# Arduino_StepperPrototype.net
KiCad netlist of a schematic drawn in Altium Designer
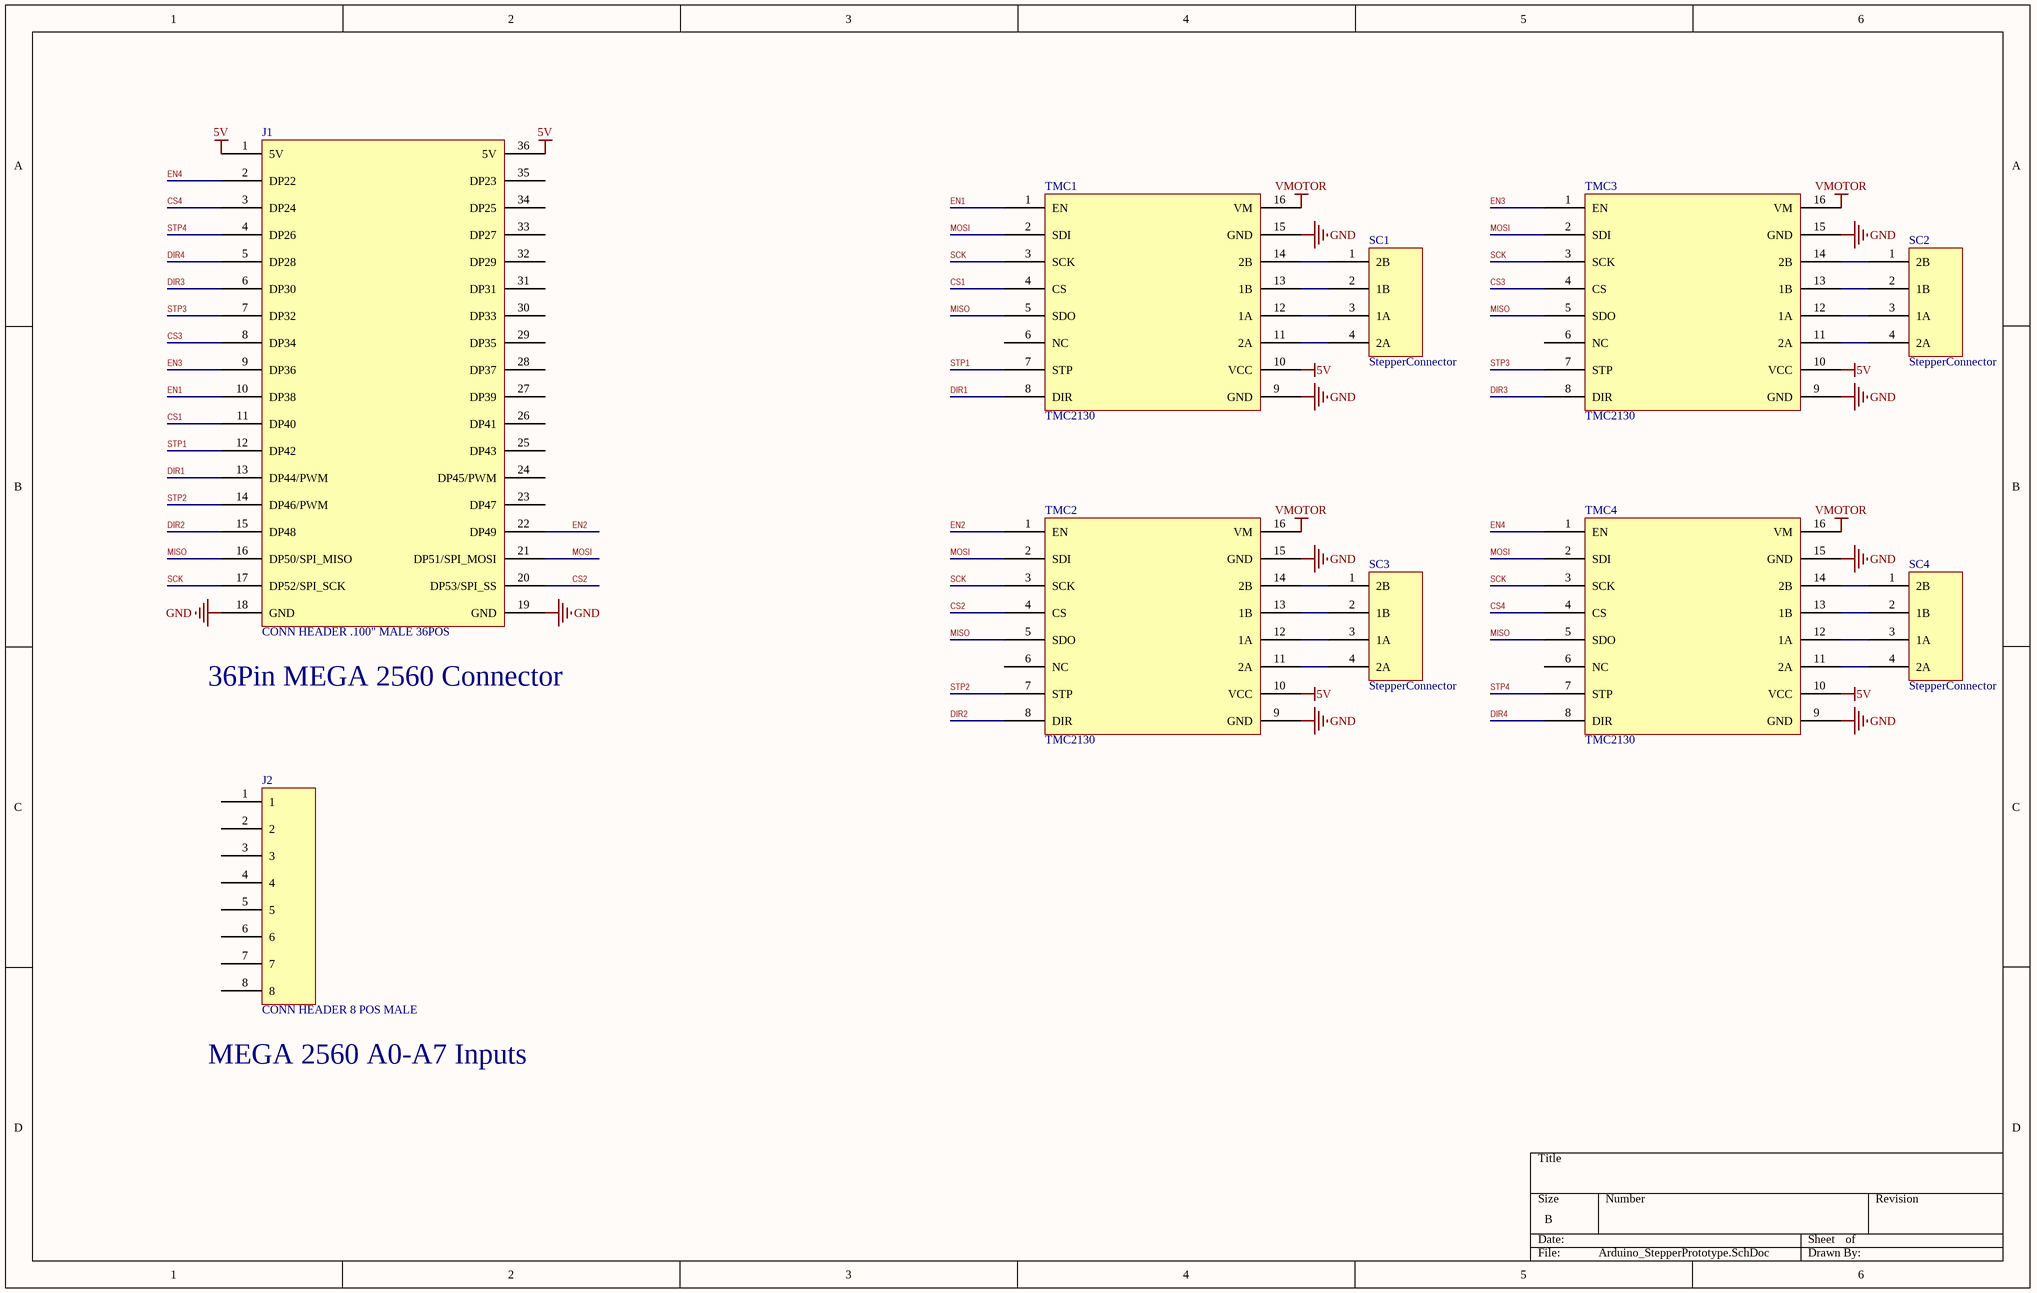
[diagram p0: Arduino_StepperPrototype.SchDoc]

(export (version "E")
  (design (tool "Eeschema 10.0.6"))
  (components
    (comp (ref "J1")
      (value "CONN HEADER .100\" MALE 36POS")
      (footprint "DIP36_MALE")
      (description "CONN HEADER .100\" DUAL STR 36POS")
      (fields
        (field (name "MANUFACTURER") "Sullins")
        (field (name "MANUFACTURER PART NUMBER") "PREC018DAAN-RC")
      )
      (libsource (lib "Arduino_StepperPrototype") (part "PREC018DAAN-RC"))
    )
    (comp (ref "J2")
      (value "CONN HEADER 8 POS MALE")
      (footprint "DIP8_MALE")
      (fields
        (field (name "MANUFACTURER") "Sullins")
        (field (name "MANUFACTURER PART NUMBER") "PREC008SAAN-RC")
      )
      (libsource (lib "Arduino_StepperPrototype") (part "PREC008SAAN-RC"))
    )
    (comp (ref "SC1")
      (value "StepperConnector")
      (footprint "DIP4")
      (libsource (lib "Arduino_StepperPrototype") (part "StepperConn"))
    )
    (comp (ref "SC2")
      (value "StepperConnector")
      (footprint "DIP4")
      (libsource (lib "Arduino_StepperPrototype") (part "StepperConn"))
    )
    (comp (ref "SC3")
      (value "StepperConnector")
      (footprint "DIP4")
      (libsource (lib "Arduino_StepperPrototype") (part "StepperConn"))
    )
    (comp (ref "SC4")
      (value "StepperConnector")
      (footprint "DIP4")
      (libsource (lib "Arduino_StepperPrototype") (part "StepperConn"))
    )
    (comp (ref "TMC1")
      (value "TMC2130")
      (footprint "DIP16_Stepper")
      (description "Knockoff SilentStepStick")
      (libsource (lib "Arduino_StepperPrototype") (part "SilentStepStick_BigTreeTech_TMC2130V1.1"))
    )
    (comp (ref "TMC2")
      (value "TMC2130")
      (footprint "DIP16_Stepper")
      (description "Knockoff SilentStepStick")
      (libsource (lib "Arduino_StepperPrototype") (part "SilentStepStick_BigTreeTech_TMC2130V1.1"))
    )
    (comp (ref "TMC3")
      (value "TMC2130")
      (footprint "DIP16_Stepper")
      (description "Knockoff SilentStepStick")
      (libsource (lib "Arduino_StepperPrototype") (part "SilentStepStick_BigTreeTech_TMC2130V1.1"))
    )
    (comp (ref "TMC4")
      (value "TMC2130")
      (footprint "DIP16_Stepper")
      (description "Knockoff SilentStepStick")
      (libsource (lib "Arduino_StepperPrototype") (part "SilentStepStick_BigTreeTech_TMC2130V1.1"))
    )
  )
  (nets
    (net (code "1") (name "/CS1") (class "Default")
      (node (ref "J1") (pin "11") (pinfunction "DP40_11") (pintype "passive"))
      (node (ref "TMC1") (pin "4") (pinfunction "CS_4") (pintype "passive"))
    )
    (net (code "2") (name "/CS2") (class "Default")
      (node (ref "J1") (pin "20") (pinfunction "DP53/SPI_SS_20") (pintype "passive"))
      (node (ref "TMC2") (pin "4") (pinfunction "CS_4") (pintype "passive"))
    )
    (net (code "3") (name "/CS3") (class "Default")
      (node (ref "J1") (pin "8") (pinfunction "DP34_8") (pintype "passive"))
      (node (ref "TMC3") (pin "4") (pinfunction "CS_4") (pintype "passive"))
    )
    (net (code "4") (name "/CS4") (class "Default")
      (node (ref "J1") (pin "3") (pinfunction "DP24_3") (pintype "passive"))
      (node (ref "TMC4") (pin "4") (pinfunction "CS_4") (pintype "passive"))
    )
    (net (code "5") (name "/DIR1") (class "Default")
      (node (ref "J1") (pin "13") (pinfunction "DP44/PWM_13") (pintype "passive"))
      (node (ref "TMC1") (pin "8") (pinfunction "DIR_8") (pintype "passive"))
    )
    (net (code "6") (name "/DIR2") (class "Default")
      (node (ref "J1") (pin "15") (pinfunction "DP48_15") (pintype "passive"))
      (node (ref "TMC2") (pin "8") (pinfunction "DIR_8") (pintype "passive"))
    )
    (net (code "7") (name "/DIR3") (class "Default")
      (node (ref "J1") (pin "6") (pinfunction "DP30_6") (pintype "passive"))
      (node (ref "TMC3") (pin "8") (pinfunction "DIR_8") (pintype "passive"))
    )
    (net (code "8") (name "/DIR4") (class "Default")
      (node (ref "J1") (pin "5") (pinfunction "DP28_5") (pintype "passive"))
      (node (ref "TMC4") (pin "8") (pinfunction "DIR_8") (pintype "passive"))
    )
    (net (code "9") (name "/EN1") (class "Default")
      (node (ref "J1") (pin "10") (pinfunction "DP38_10") (pintype "passive"))
      (node (ref "TMC1") (pin "1") (pinfunction "EN_1") (pintype "passive"))
    )
    (net (code "10") (name "/EN2") (class "Default")
      (node (ref "J1") (pin "22") (pinfunction "DP49_22") (pintype "passive"))
      (node (ref "TMC2") (pin "1") (pinfunction "EN_1") (pintype "passive"))
    )
    (net (code "11") (name "/EN3") (class "Default")
      (node (ref "J1") (pin "9") (pinfunction "DP36_9") (pintype "passive"))
      (node (ref "TMC3") (pin "1") (pinfunction "EN_1") (pintype "passive"))
    )
    (net (code "12") (name "/EN4") (class "Default")
      (node (ref "J1") (pin "2") (pinfunction "DP22_2") (pintype "passive"))
      (node (ref "TMC4") (pin "1") (pinfunction "EN_1") (pintype "passive"))
    )
    (net (code "13") (name "/MISO") (class "Default")
      (node (ref "J1") (pin "16") (pinfunction "DP50/SPI_MISO_16") (pintype "passive"))
      (node (ref "TMC1") (pin "5") (pinfunction "SDO_5") (pintype "passive"))
      (node (ref "TMC2") (pin "5") (pinfunction "SDO_5") (pintype "passive"))
      (node (ref "TMC3") (pin "5") (pinfunction "SDO_5") (pintype "passive"))
      (node (ref "TMC4") (pin "5") (pinfunction "SDO_5") (pintype "passive"))
    )
    (net (code "14") (name "/MOSI") (class "Default")
      (node (ref "J1") (pin "21") (pinfunction "DP51/SPI_MOSI_21") (pintype "passive"))
      (node (ref "TMC1") (pin "2") (pinfunction "SDI_2") (pintype "passive"))
      (node (ref "TMC2") (pin "2") (pinfunction "SDI_2") (pintype "passive"))
      (node (ref "TMC3") (pin "2") (pinfunction "SDI_2") (pintype "passive"))
      (node (ref "TMC4") (pin "2") (pinfunction "SDI_2") (pintype "passive"))
    )
    (net (code "15") (name "/SCK") (class "Default")
      (node (ref "J1") (pin "17") (pinfunction "DP52/SPI_SCK_17") (pintype "passive"))
      (node (ref "TMC1") (pin "3") (pinfunction "SCK_3") (pintype "passive"))
      (node (ref "TMC2") (pin "3") (pinfunction "SCK_3") (pintype "passive"))
      (node (ref "TMC3") (pin "3") (pinfunction "SCK_3") (pintype "passive"))
      (node (ref "TMC4") (pin "3") (pinfunction "SCK_3") (pintype "passive"))
    )
    (net (code "16") (name "/STP1") (class "Default")
      (node (ref "J1") (pin "12") (pinfunction "DP42_12") (pintype "passive"))
      (node (ref "TMC1") (pin "7") (pinfunction "STP_7") (pintype "passive"))
    )
    (net (code "17") (name "/STP2") (class "Default")
      (node (ref "J1") (pin "14") (pinfunction "DP46/PWM_14") (pintype "passive"))
      (node (ref "TMC2") (pin "7") (pinfunction "STP_7") (pintype "passive"))
    )
    (net (code "18") (name "/STP3") (class "Default")
      (node (ref "J1") (pin "7") (pinfunction "DP32_7") (pintype "passive"))
      (node (ref "TMC3") (pin "7") (pinfunction "STP_7") (pintype "passive"))
    )
    (net (code "19") (name "/STP4") (class "Default")
      (node (ref "J1") (pin "4") (pinfunction "DP26_4") (pintype "passive"))
      (node (ref "TMC4") (pin "7") (pinfunction "STP_7") (pintype "passive"))
    )
    (net (code "20") (name "5V") (class "Default")
      (node (ref "J1") (pin "1") (pinfunction "5V_1") (pintype "passive"))
      (node (ref "J1") (pin "36") (pinfunction "5V_36") (pintype "passive"))
      (node (ref "TMC1") (pin "10") (pinfunction "VCC_10") (pintype "passive"))
      (node (ref "TMC2") (pin "10") (pinfunction "VCC_10") (pintype "passive"))
      (node (ref "TMC3") (pin "10") (pinfunction "VCC_10") (pintype "passive"))
      (node (ref "TMC4") (pin "10") (pinfunction "VCC_10") (pintype "passive"))
    )
    (net (code "21") (name "GND") (class "Default")
      (node (ref "J1") (pin "18") (pinfunction "GND_18") (pintype "passive"))
      (node (ref "J1") (pin "19") (pinfunction "GND_19") (pintype "passive"))
      (node (ref "TMC1") (pin "15") (pinfunction "GND_15") (pintype "passive"))
      (node (ref "TMC1") (pin "9") (pinfunction "GND_9") (pintype "passive"))
      (node (ref "TMC2") (pin "15") (pinfunction "GND_15") (pintype "passive"))
      (node (ref "TMC2") (pin "9") (pinfunction "GND_9") (pintype "passive"))
      (node (ref "TMC3") (pin "15") (pinfunction "GND_15") (pintype "passive"))
      (node (ref "TMC3") (pin "9") (pinfunction "GND_9") (pintype "passive"))
      (node (ref "TMC4") (pin "15") (pinfunction "GND_15") (pintype "passive"))
      (node (ref "TMC4") (pin "9") (pinfunction "GND_9") (pintype "passive"))
    )
    (net (code "22") (name "Net-(SC1-1A)") (class "Default")
      (node (ref "SC1") (pin "3") (pinfunction "1A_3") (pintype "passive"))
      (node (ref "TMC1") (pin "12") (pinfunction "1A_12") (pintype "passive"))
    )
    (net (code "23") (name "Net-(SC1-1B)") (class "Default")
      (node (ref "SC1") (pin "2") (pinfunction "1B_2") (pintype "passive"))
      (node (ref "TMC1") (pin "13") (pinfunction "1B_13") (pintype "passive"))
    )
    (net (code "24") (name "Net-(SC1-2A)") (class "Default")
      (node (ref "SC1") (pin "4") (pinfunction "2A_4") (pintype "passive"))
      (node (ref "TMC1") (pin "11") (pinfunction "2A_11") (pintype "passive"))
    )
    (net (code "25") (name "Net-(SC1-2B)") (class "Default")
      (node (ref "SC1") (pin "1") (pinfunction "2B_1") (pintype "passive"))
      (node (ref "TMC1") (pin "14") (pinfunction "2B_14") (pintype "passive"))
    )
    (net (code "26") (name "Net-(SC2-1A)") (class "Default")
      (node (ref "SC2") (pin "3") (pinfunction "1A_3") (pintype "passive"))
      (node (ref "TMC3") (pin "12") (pinfunction "1A_12") (pintype "passive"))
    )
    (net (code "27") (name "Net-(SC2-1B)") (class "Default")
      (node (ref "SC2") (pin "2") (pinfunction "1B_2") (pintype "passive"))
      (node (ref "TMC3") (pin "13") (pinfunction "1B_13") (pintype "passive"))
    )
    (net (code "28") (name "Net-(SC2-2A)") (class "Default")
      (node (ref "SC2") (pin "4") (pinfunction "2A_4") (pintype "passive"))
      (node (ref "TMC3") (pin "11") (pinfunction "2A_11") (pintype "passive"))
    )
    (net (code "29") (name "Net-(SC2-2B)") (class "Default")
      (node (ref "SC2") (pin "1") (pinfunction "2B_1") (pintype "passive"))
      (node (ref "TMC3") (pin "14") (pinfunction "2B_14") (pintype "passive"))
    )
    (net (code "30") (name "Net-(SC3-1A)") (class "Default")
      (node (ref "SC3") (pin "3") (pinfunction "1A_3") (pintype "passive"))
      (node (ref "TMC2") (pin "12") (pinfunction "1A_12") (pintype "passive"))
    )
    (net (code "31") (name "Net-(SC3-1B)") (class "Default")
      (node (ref "SC3") (pin "2") (pinfunction "1B_2") (pintype "passive"))
      (node (ref "TMC2") (pin "13") (pinfunction "1B_13") (pintype "passive"))
    )
    (net (code "32") (name "Net-(SC3-2A)") (class "Default")
      (node (ref "SC3") (pin "4") (pinfunction "2A_4") (pintype "passive"))
      (node (ref "TMC2") (pin "11") (pinfunction "2A_11") (pintype "passive"))
    )
    (net (code "33") (name "Net-(SC3-2B)") (class "Default")
      (node (ref "SC3") (pin "1") (pinfunction "2B_1") (pintype "passive"))
      (node (ref "TMC2") (pin "14") (pinfunction "2B_14") (pintype "passive"))
    )
    (net (code "34") (name "Net-(SC4-1A)") (class "Default")
      (node (ref "SC4") (pin "3") (pinfunction "1A_3") (pintype "passive"))
      (node (ref "TMC4") (pin "12") (pinfunction "1A_12") (pintype "passive"))
    )
    (net (code "35") (name "Net-(SC4-1B)") (class "Default")
      (node (ref "SC4") (pin "2") (pinfunction "1B_2") (pintype "passive"))
      (node (ref "TMC4") (pin "13") (pinfunction "1B_13") (pintype "passive"))
    )
    (net (code "36") (name "Net-(SC4-2A)") (class "Default")
      (node (ref "SC4") (pin "4") (pinfunction "2A_4") (pintype "passive"))
      (node (ref "TMC4") (pin "11") (pinfunction "2A_11") (pintype "passive"))
    )
    (net (code "37") (name "Net-(SC4-2B)") (class "Default")
      (node (ref "SC4") (pin "1") (pinfunction "2B_1") (pintype "passive"))
      (node (ref "TMC4") (pin "14") (pinfunction "2B_14") (pintype "passive"))
    )
    (net (code "38") (name "VMOTOR") (class "Default")
      (node (ref "TMC1") (pin "16") (pinfunction "VM_16") (pintype "passive"))
      (node (ref "TMC2") (pin "16") (pinfunction "VM_16") (pintype "passive"))
      (node (ref "TMC3") (pin "16") (pinfunction "VM_16") (pintype "passive"))
      (node (ref "TMC4") (pin "16") (pinfunction "VM_16") (pintype "passive"))
    )
    (net (code "39") (name "unconnected-(J1-DP23-Pad35)") (class "Default")
      (node (ref "J1") (pin "35") (pinfunction "DP23_35") (pintype "passive"))
    )
    (net (code "40") (name "unconnected-(J1-DP25-Pad34)") (class "Default")
      (node (ref "J1") (pin "34") (pinfunction "DP25_34") (pintype "passive"))
    )
    (net (code "41") (name "unconnected-(J1-DP27-Pad33)") (class "Default")
      (node (ref "J1") (pin "33") (pinfunction "DP27_33") (pintype "passive"))
    )
    (net (code "42") (name "unconnected-(J1-DP29-Pad32)") (class "Default")
      (node (ref "J1") (pin "32") (pinfunction "DP29_32") (pintype "passive"))
    )
    (net (code "43") (name "unconnected-(J1-DP31-Pad31)") (class "Default")
      (node (ref "J1") (pin "31") (pinfunction "DP31_31") (pintype "passive"))
    )
    (net (code "44") (name "unconnected-(J1-DP33-Pad30)") (class "Default")
      (node (ref "J1") (pin "30") (pinfunction "DP33_30") (pintype "passive"))
    )
    (net (code "45") (name "unconnected-(J1-DP35-Pad29)") (class "Default")
      (node (ref "J1") (pin "29") (pinfunction "DP35_29") (pintype "passive"))
    )
    (net (code "46") (name "unconnected-(J1-DP37-Pad28)") (class "Default")
      (node (ref "J1") (pin "28") (pinfunction "DP37_28") (pintype "passive"))
    )
    (net (code "47") (name "unconnected-(J1-DP39-Pad27)") (class "Default")
      (node (ref "J1") (pin "27") (pinfunction "DP39_27") (pintype "passive"))
    )
    (net (code "48") (name "unconnected-(J1-DP41-Pad26)") (class "Default")
      (node (ref "J1") (pin "26") (pinfunction "DP41_26") (pintype "passive"))
    )
    (net (code "49") (name "unconnected-(J1-DP43-Pad25)") (class "Default")
      (node (ref "J1") (pin "25") (pinfunction "DP43_25") (pintype "passive"))
    )
    (net (code "50") (name "unconnected-(J1-DP45{slash}PWM-Pad24)") (class "Default")
      (node (ref "J1") (pin "24") (pinfunction "DP45/PWM_24") (pintype "passive"))
    )
    (net (code "51") (name "unconnected-(J1-DP47-Pad23)") (class "Default")
      (node (ref "J1") (pin "23") (pinfunction "DP47_23") (pintype "passive"))
    )
    (net (code "52") (name "unconnected-(J2-Pad1)") (class "Default")
      (node (ref "J2") (pin "1") (pinfunction "1_1") (pintype "passive"))
    )
    (net (code "53") (name "unconnected-(J2-Pad2)") (class "Default")
      (node (ref "J2") (pin "2") (pinfunction "2_2") (pintype "passive"))
    )
    (net (code "54") (name "unconnected-(J2-Pad3)") (class "Default")
      (node (ref "J2") (pin "3") (pinfunction "3_3") (pintype "passive"))
    )
    (net (code "55") (name "unconnected-(J2-Pad4)") (class "Default")
      (node (ref "J2") (pin "4") (pinfunction "4_4") (pintype "passive"))
    )
    (net (code "56") (name "unconnected-(J2-Pad5)") (class "Default")
      (node (ref "J2") (pin "5") (pinfunction "5_5") (pintype "passive"))
    )
    (net (code "57") (name "unconnected-(J2-Pad6)") (class "Default")
      (node (ref "J2") (pin "6") (pinfunction "6_6") (pintype "passive"))
    )
    (net (code "58") (name "unconnected-(J2-Pad7)") (class "Default")
      (node (ref "J2") (pin "7") (pinfunction "7_7") (pintype "passive"))
    )
    (net (code "59") (name "unconnected-(J2-Pad8)") (class "Default")
      (node (ref "J2") (pin "8") (pinfunction "8_8") (pintype "passive"))
    )
    (net (code "60") (name "unconnected-(TMC1-NC-Pad6)") (class "Default")
      (node (ref "TMC1") (pin "6") (pinfunction "NC_6") (pintype "passive"))
    )
    (net (code "61") (name "unconnected-(TMC2-NC-Pad6)") (class "Default")
      (node (ref "TMC2") (pin "6") (pinfunction "NC_6") (pintype "passive"))
    )
    (net (code "62") (name "unconnected-(TMC3-NC-Pad6)") (class "Default")
      (node (ref "TMC3") (pin "6") (pinfunction "NC_6") (pintype "passive"))
    )
    (net (code "63") (name "unconnected-(TMC4-NC-Pad6)") (class "Default")
      (node (ref "TMC4") (pin "6") (pinfunction "NC_6") (pintype "passive"))
    )
  )
)
